# PWM.net
KiCad netlist of a schematic drawn in EAGLE
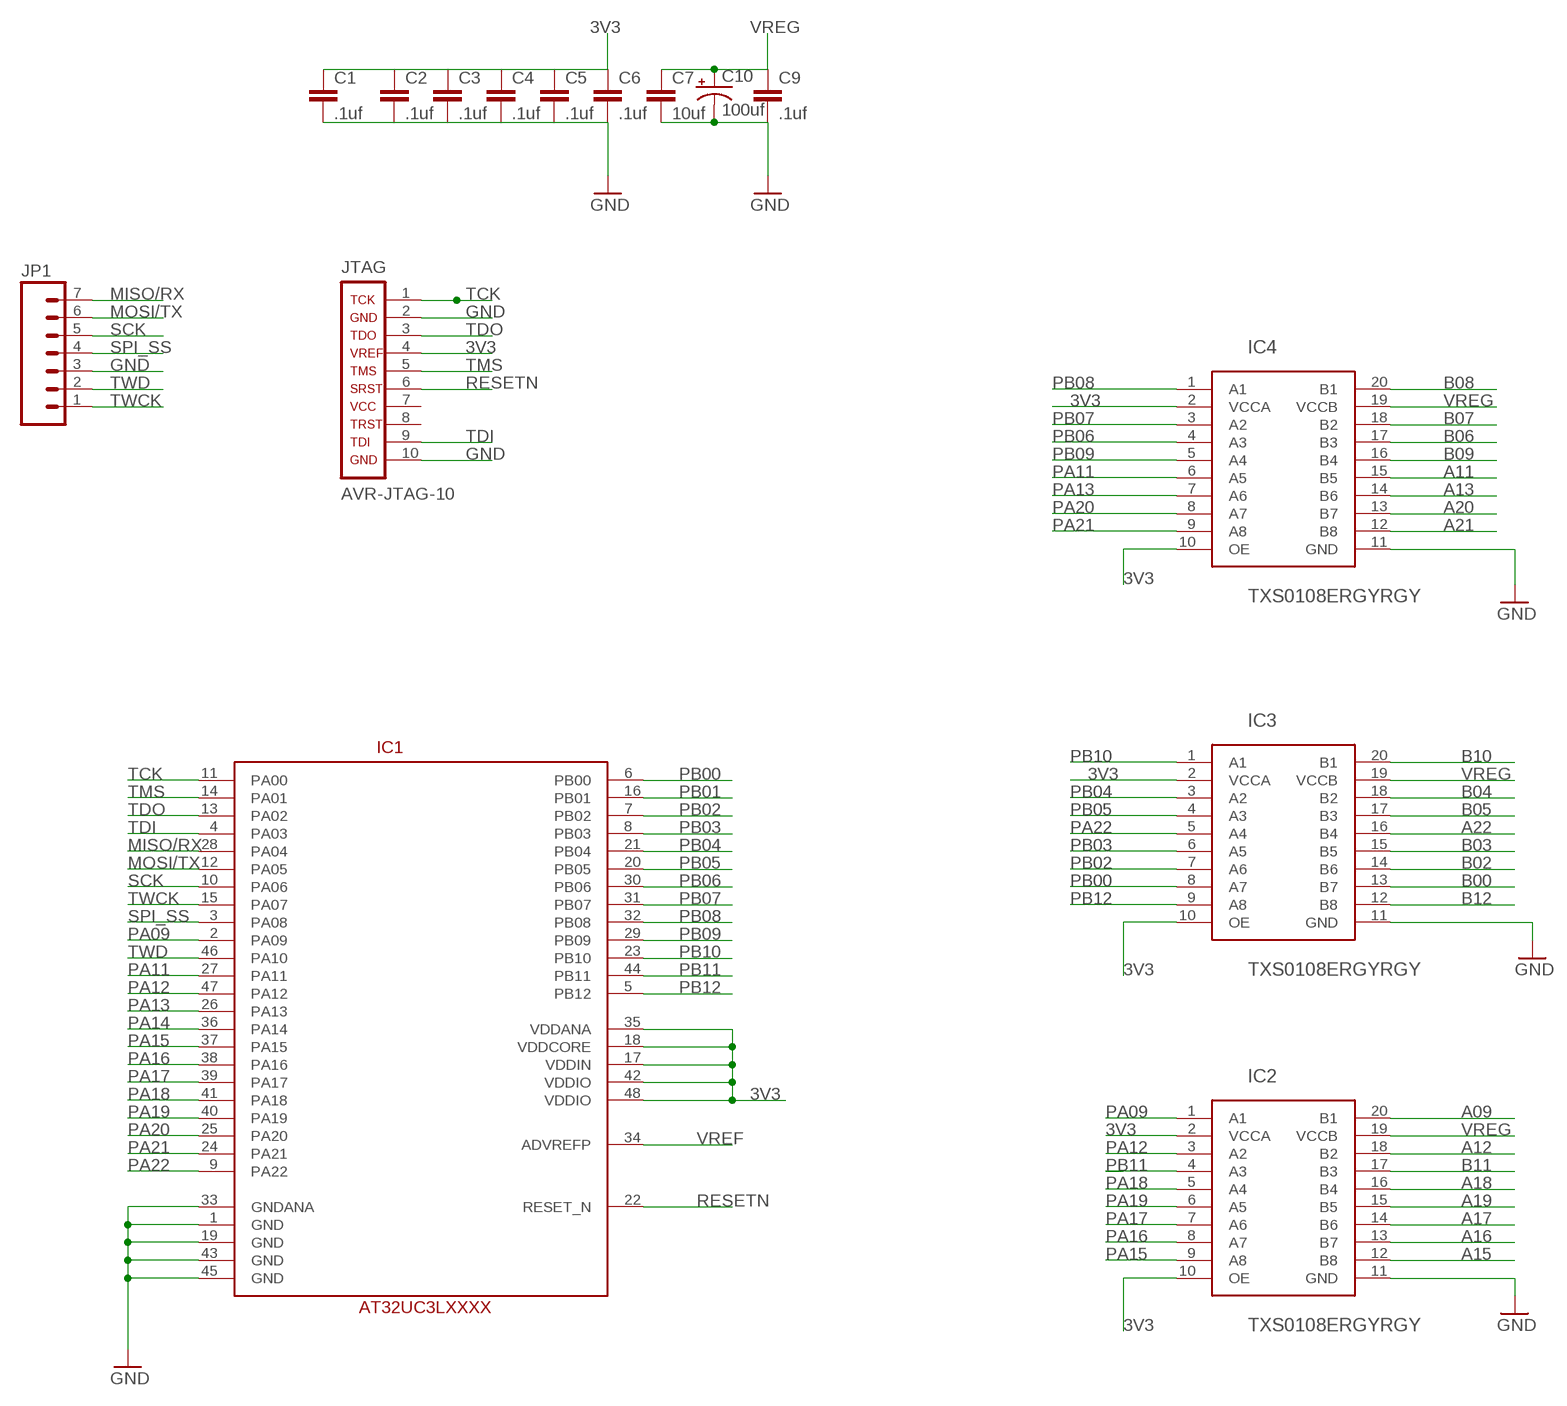
[diagram p0: schematic, sheet 1]
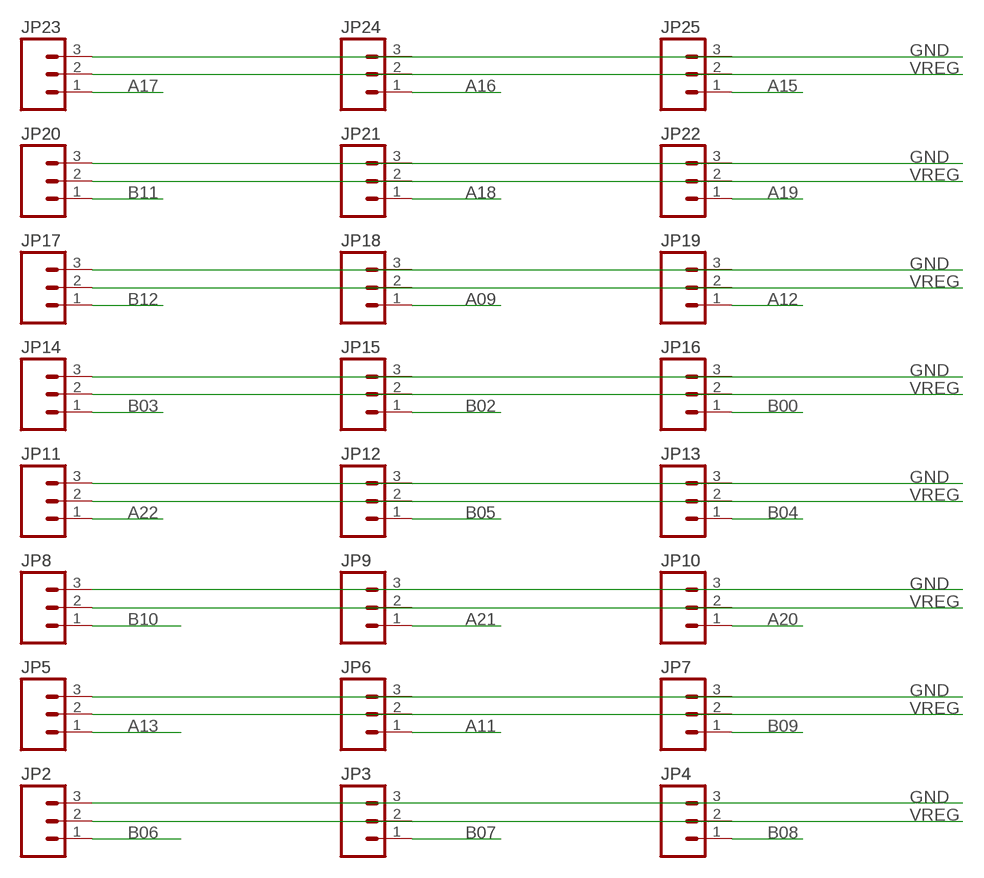
[diagram p1: schematic, sheet 2]
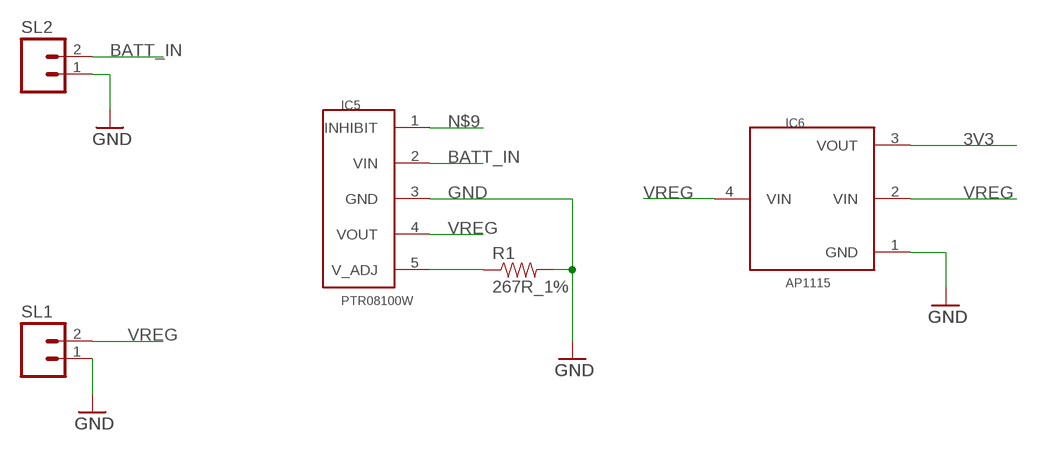
[diagram p2: schematic, sheet 3]

(export (version "E")
  (design (tool "Eeschema 10.0.6"))
  (components
    (comp (ref "IC5")
      (value "PTR08100W")
      (footprint "eagle-import:SLTS284E")
      (libsource (lib "eagle-import") (part "SLTS284ETI"))
    )
    (comp (ref "IC6")
      (value "AP1115")
      (footprint "eagle-import:SOT89-3L")
      (libsource (lib "eagle-import") (part "AP1115"))
    )
    (comp (ref "R1")
      (value "267R_1%")
      (footprint "eagle-import:0805")
      (libsource (lib "eagle-import") (part "RESISTOR0805-RES"))
    )
    (comp (ref "SL1")
      (value "M02")
      (footprint "eagle-import:02P")
      (libsource (lib "eagle-import") (part "M02"))
    )
    (comp (ref "SL2")
      (value "M02")
      (footprint "eagle-import:02P")
      (libsource (lib "eagle-import") (part "M02"))
    )
    (comp (ref "C1")
      (value ".1uf")
      (footprint "eagle-import:0805")
      (libsource (lib "eagle-import") (part "CAP0805"))
    )
    (comp (ref "C2")
      (value ".1uf")
      (footprint "eagle-import:0805")
      (libsource (lib "eagle-import") (part "CAP0805"))
    )
    (comp (ref "C3")
      (value ".1uf")
      (footprint "eagle-import:0805")
      (libsource (lib "eagle-import") (part "CAP0805"))
    )
    (comp (ref "C4")
      (value ".1uf")
      (footprint "eagle-import:0805")
      (libsource (lib "eagle-import") (part "CAP0805"))
    )
    (comp (ref "C5")
      (value ".1uf")
      (footprint "eagle-import:0805")
      (libsource (lib "eagle-import") (part "CAP0805"))
    )
    (comp (ref "C6")
      (value ".1uf")
      (footprint "eagle-import:0805")
      (libsource (lib "eagle-import") (part "CAP0805"))
    )
    (comp (ref "C7")
      (value "10uf")
      (footprint "eagle-import:0805")
      (libsource (lib "eagle-import") (part "CAP0805"))
    )
    (comp (ref "C9")
      (value ".1uf")
      (footprint "eagle-import:0805")
      (libsource (lib "eagle-import") (part "CAP0805"))
    )
    (comp (ref "C10")
      (value "100uf")
      (footprint "eagle-import:EIA7343")
      (libsource (lib "eagle-import") (part "CAP_POL7343"))
    )
    (comp (ref "IC1")
      (value "AT32UC3L016/32/64")
      (footprint "eagle-import:TQFP48")
      (libsource (lib "eagle-import") (part "AT32UC3L016/32/64"))
    )
    (comp (ref "IC2")
      (value "TXS0108ERGYRGY")
      (footprint "eagle-import:RGY")
      (libsource (lib "eagle-import") (part "TXS0108ERGYRGY"))
    )
    (comp (ref "IC3")
      (value "TXS0108ERGYRGY")
      (footprint "eagle-import:RGY")
      (libsource (lib "eagle-import") (part "TXS0108ERGYRGY"))
    )
    (comp (ref "IC4")
      (value "TXS0108ERGYRGY")
      (footprint "eagle-import:RGY")
      (libsource (lib "eagle-import") (part "TXS0108ERGYRGY"))
    )
    (comp (ref "JP1")
      (value "M07")
      (footprint "eagle-import:1X07")
      (libsource (lib "eagle-import") (part "M07"))
    )
    (comp (ref "JTAG")
      (value "AVR-JTAG-10")
      (footprint "eagle-import:AVR-JTAG-10")
      (libsource (lib "eagle-import") (part "AVR-JTAG-10"))
    )
    (comp (ref "JP2")
      (value "M03PTH")
      (footprint "eagle-import:1X03")
      (libsource (lib "eagle-import") (part "M03PTH"))
    )
    (comp (ref "JP3")
      (value "M03PTH")
      (footprint "eagle-import:1X03")
      (libsource (lib "eagle-import") (part "M03PTH"))
    )
    (comp (ref "JP4")
      (value "M03PTH")
      (footprint "eagle-import:1X03")
      (libsource (lib "eagle-import") (part "M03PTH"))
    )
    (comp (ref "JP5")
      (value "M03PTH")
      (footprint "eagle-import:1X03")
      (libsource (lib "eagle-import") (part "M03PTH"))
    )
    (comp (ref "JP6")
      (value "M03PTH")
      (footprint "eagle-import:1X03")
      (libsource (lib "eagle-import") (part "M03PTH"))
    )
    (comp (ref "JP7")
      (value "M03PTH")
      (footprint "eagle-import:1X03")
      (libsource (lib "eagle-import") (part "M03PTH"))
    )
    (comp (ref "JP8")
      (value "M03PTH")
      (footprint "eagle-import:1X03")
      (libsource (lib "eagle-import") (part "M03PTH"))
    )
    (comp (ref "JP9")
      (value "M03PTH")
      (footprint "eagle-import:1X03")
      (libsource (lib "eagle-import") (part "M03PTH"))
    )
    (comp (ref "JP10")
      (value "M03PTH")
      (footprint "eagle-import:1X03")
      (libsource (lib "eagle-import") (part "M03PTH"))
    )
    (comp (ref "JP11")
      (value "M03PTH")
      (footprint "eagle-import:1X03")
      (libsource (lib "eagle-import") (part "M03PTH"))
    )
    (comp (ref "JP12")
      (value "M03PTH")
      (footprint "eagle-import:1X03")
      (libsource (lib "eagle-import") (part "M03PTH"))
    )
    (comp (ref "JP13")
      (value "M03PTH")
      (footprint "eagle-import:1X03")
      (libsource (lib "eagle-import") (part "M03PTH"))
    )
    (comp (ref "JP14")
      (value "M03PTH")
      (footprint "eagle-import:1X03")
      (libsource (lib "eagle-import") (part "M03PTH"))
    )
    (comp (ref "JP15")
      (value "M03PTH")
      (footprint "eagle-import:1X03")
      (libsource (lib "eagle-import") (part "M03PTH"))
    )
    (comp (ref "JP16")
      (value "M03PTH")
      (footprint "eagle-import:1X03")
      (libsource (lib "eagle-import") (part "M03PTH"))
    )
    (comp (ref "JP17")
      (value "M03PTH")
      (footprint "eagle-import:1X03")
      (libsource (lib "eagle-import") (part "M03PTH"))
    )
    (comp (ref "JP18")
      (value "M03PTH")
      (footprint "eagle-import:1X03")
      (libsource (lib "eagle-import") (part "M03PTH"))
    )
    (comp (ref "JP19")
      (value "M03PTH")
      (footprint "eagle-import:1X03")
      (libsource (lib "eagle-import") (part "M03PTH"))
    )
    (comp (ref "JP20")
      (value "M03PTH")
      (footprint "eagle-import:1X03")
      (libsource (lib "eagle-import") (part "M03PTH"))
    )
    (comp (ref "JP21")
      (value "M03PTH")
      (footprint "eagle-import:1X03")
      (libsource (lib "eagle-import") (part "M03PTH"))
    )
    (comp (ref "JP22")
      (value "M03PTH")
      (footprint "eagle-import:1X03")
      (libsource (lib "eagle-import") (part "M03PTH"))
    )
    (comp (ref "JP23")
      (value "M03PTH")
      (footprint "eagle-import:1X03")
      (libsource (lib "eagle-import") (part "M03PTH"))
    )
    (comp (ref "JP24")
      (value "M03PTH")
      (footprint "eagle-import:1X03")
      (libsource (lib "eagle-import") (part "M03PTH"))
    )
    (comp (ref "JP25")
      (value "M03PTH")
      (footprint "eagle-import:1X03")
      (libsource (lib "eagle-import") (part "M03PTH"))
    )
  )
  (nets
    (net (code "1") (name "3V3") (class "Default")
      (node (ref "C1") (pin "1") (pinfunction "1_1") (pintype "passive"))
      (node (ref "C2") (pin "1") (pinfunction "1_1") (pintype "passive"))
      (node (ref "C3") (pin "1") (pinfunction "1_1") (pintype "passive"))
      (node (ref "C4") (pin "1") (pinfunction "1_1") (pintype "passive"))
      (node (ref "C5") (pin "1") (pinfunction "1_1") (pintype "passive"))
      (node (ref "C6") (pin "1") (pinfunction "1_1") (pintype "passive"))
      (node (ref "IC1") (pin "17") (pinfunction "VDDIN_17") (pintype "bidirectional"))
      (node (ref "IC1") (pin "18") (pinfunction "VDDCORE_18") (pintype "bidirectional"))
      (node (ref "IC1") (pin "35") (pinfunction "VDDANA_35") (pintype "bidirectional"))
      (node (ref "IC1") (pin "42") (pinfunction "VDDIO_42") (pintype "bidirectional"))
      (node (ref "IC1") (pin "48") (pinfunction "VDDIO_48") (pintype "bidirectional"))
      (node (ref "IC2") (pin "10") (pinfunction "OE_10") (pintype "bidirectional"))
      (node (ref "IC2") (pin "2") (pinfunction "VCCA_2") (pintype "bidirectional"))
      (node (ref "IC3") (pin "10") (pinfunction "OE_10") (pintype "bidirectional"))
      (node (ref "IC3") (pin "2") (pinfunction "VCCA_2") (pintype "bidirectional"))
      (node (ref "IC4") (pin "10") (pinfunction "OE_10") (pintype "bidirectional"))
      (node (ref "IC4") (pin "2") (pinfunction "VCCA_2") (pintype "bidirectional"))
      (node (ref "IC6") (pin "3") (pinfunction "VOUT_3") (pintype "bidirectional"))
      (node (ref "JTAG") (pin "4") (pinfunction "4_4") (pintype "passive"))
    )
    (net (code "2") (name "A09") (class "Default")
      (node (ref "IC2") (pin "20") (pinfunction "B1_20") (pintype "bidirectional"))
      (node (ref "JP18") (pin "1") (pinfunction "1_1") (pintype "passive"))
    )
    (net (code "3") (name "A11") (class "Default")
      (node (ref "IC4") (pin "15") (pinfunction "B5_15") (pintype "bidirectional"))
      (node (ref "JP6") (pin "1") (pinfunction "1_1") (pintype "passive"))
    )
    (net (code "4") (name "A12") (class "Default")
      (node (ref "IC2") (pin "18") (pinfunction "B2_18") (pintype "bidirectional"))
      (node (ref "JP19") (pin "1") (pinfunction "1_1") (pintype "passive"))
    )
    (net (code "5") (name "A13") (class "Default")
      (node (ref "IC4") (pin "14") (pinfunction "B6_14") (pintype "bidirectional"))
      (node (ref "JP5") (pin "1") (pinfunction "1_1") (pintype "passive"))
    )
    (net (code "6") (name "A15") (class "Default")
      (node (ref "IC2") (pin "12") (pinfunction "B8_12") (pintype "bidirectional"))
      (node (ref "JP25") (pin "1") (pinfunction "1_1") (pintype "passive"))
    )
    (net (code "7") (name "A16") (class "Default")
      (node (ref "IC2") (pin "13") (pinfunction "B7_13") (pintype "bidirectional"))
      (node (ref "JP24") (pin "1") (pinfunction "1_1") (pintype "passive"))
    )
    (net (code "8") (name "A17") (class "Default")
      (node (ref "IC2") (pin "14") (pinfunction "B6_14") (pintype "bidirectional"))
      (node (ref "JP23") (pin "1") (pinfunction "1_1") (pintype "passive"))
    )
    (net (code "9") (name "A18") (class "Default")
      (node (ref "IC2") (pin "16") (pinfunction "B4_16") (pintype "bidirectional"))
      (node (ref "JP21") (pin "1") (pinfunction "1_1") (pintype "passive"))
    )
    (net (code "10") (name "A19") (class "Default")
      (node (ref "IC2") (pin "15") (pinfunction "B5_15") (pintype "bidirectional"))
      (node (ref "JP22") (pin "1") (pinfunction "1_1") (pintype "passive"))
    )
    (net (code "11") (name "A20") (class "Default")
      (node (ref "IC4") (pin "13") (pinfunction "B7_13") (pintype "bidirectional"))
      (node (ref "JP10") (pin "1") (pinfunction "1_1") (pintype "passive"))
    )
    (net (code "12") (name "A21") (class "Default")
      (node (ref "IC4") (pin "12") (pinfunction "B8_12") (pintype "bidirectional"))
      (node (ref "JP9") (pin "1") (pinfunction "1_1") (pintype "passive"))
    )
    (net (code "13") (name "A22") (class "Default")
      (node (ref "IC3") (pin "16") (pinfunction "B4_16") (pintype "bidirectional"))
      (node (ref "JP11") (pin "1") (pinfunction "1_1") (pintype "passive"))
    )
    (net (code "14") (name "B00") (class "Default")
      (node (ref "IC3") (pin "13") (pinfunction "B7_13") (pintype "bidirectional"))
      (node (ref "JP16") (pin "1") (pinfunction "1_1") (pintype "passive"))
    )
    (net (code "15") (name "B02") (class "Default")
      (node (ref "IC3") (pin "14") (pinfunction "B6_14") (pintype "bidirectional"))
      (node (ref "JP15") (pin "1") (pinfunction "1_1") (pintype "passive"))
    )
    (net (code "16") (name "B03") (class "Default")
      (node (ref "IC3") (pin "15") (pinfunction "B5_15") (pintype "bidirectional"))
      (node (ref "JP14") (pin "1") (pinfunction "1_1") (pintype "passive"))
    )
    (net (code "17") (name "B04") (class "Default")
      (node (ref "IC3") (pin "18") (pinfunction "B2_18") (pintype "bidirectional"))
      (node (ref "JP13") (pin "1") (pinfunction "1_1") (pintype "passive"))
    )
    (net (code "18") (name "B05") (class "Default")
      (node (ref "IC3") (pin "17") (pinfunction "B3_17") (pintype "bidirectional"))
      (node (ref "JP12") (pin "1") (pinfunction "1_1") (pintype "passive"))
    )
    (net (code "19") (name "B06") (class "Default")
      (node (ref "IC4") (pin "17") (pinfunction "B3_17") (pintype "bidirectional"))
      (node (ref "JP2") (pin "1") (pinfunction "1_1") (pintype "passive"))
    )
    (net (code "20") (name "B07") (class "Default")
      (node (ref "IC4") (pin "18") (pinfunction "B2_18") (pintype "bidirectional"))
      (node (ref "JP3") (pin "1") (pinfunction "1_1") (pintype "passive"))
    )
    (net (code "21") (name "B08") (class "Default")
      (node (ref "IC4") (pin "20") (pinfunction "B1_20") (pintype "bidirectional"))
      (node (ref "JP4") (pin "1") (pinfunction "1_1") (pintype "passive"))
    )
    (net (code "22") (name "B09") (class "Default")
      (node (ref "IC4") (pin "16") (pinfunction "B4_16") (pintype "bidirectional"))
      (node (ref "JP7") (pin "1") (pinfunction "1_1") (pintype "passive"))
    )
    (net (code "23") (name "B10") (class "Default")
      (node (ref "IC3") (pin "20") (pinfunction "B1_20") (pintype "bidirectional"))
      (node (ref "JP8") (pin "1") (pinfunction "1_1") (pintype "passive"))
    )
    (net (code "24") (name "B11") (class "Default")
      (node (ref "IC2") (pin "17") (pinfunction "B3_17") (pintype "bidirectional"))
      (node (ref "JP20") (pin "1") (pinfunction "1_1") (pintype "passive"))
    )
    (net (code "25") (name "B12") (class "Default")
      (node (ref "IC3") (pin "12") (pinfunction "B8_12") (pintype "bidirectional"))
      (node (ref "JP17") (pin "1") (pinfunction "1_1") (pintype "passive"))
    )
    (net (code "26") (name "BATT_IN") (class "Default")
      (node (ref "IC5") (pin "2") (pinfunction "VIN_2") (pintype "bidirectional"))
      (node (ref "SL2") (pin "2") (pinfunction "2_2") (pintype "passive"))
    )
    (net (code "27") (name "GND") (class "Default")
      (node (ref "C1") (pin "2") (pinfunction "2_2") (pintype "passive"))
      (node (ref "C10") (pin "C") (pinfunction "-_C") (pintype "passive"))
      (node (ref "C2") (pin "2") (pinfunction "2_2") (pintype "passive"))
      (node (ref "C3") (pin "2") (pinfunction "2_2") (pintype "passive"))
      (node (ref "C4") (pin "2") (pinfunction "2_2") (pintype "passive"))
      (node (ref "C5") (pin "2") (pinfunction "2_2") (pintype "passive"))
      (node (ref "C6") (pin "2") (pinfunction "2_2") (pintype "passive"))
      (node (ref "C7") (pin "2") (pinfunction "2_2") (pintype "passive"))
      (node (ref "C9") (pin "2") (pinfunction "2_2") (pintype "passive"))
      (node (ref "IC1") (pin "1") (pinfunction "GND_1") (pintype "bidirectional"))
      (node (ref "IC1") (pin "19") (pinfunction "GND_19") (pintype "bidirectional"))
      (node (ref "IC1") (pin "33") (pinfunction "GNDANA_33") (pintype "bidirectional"))
      (node (ref "IC1") (pin "43") (pinfunction "GND_43") (pintype "bidirectional"))
      (node (ref "IC1") (pin "45") (pinfunction "GND_45") (pintype "bidirectional"))
      (node (ref "IC2") (pin "11") (pinfunction "GND_11") (pintype "bidirectional"))
      (node (ref "IC3") (pin "11") (pinfunction "GND_11") (pintype "bidirectional"))
      (node (ref "IC4") (pin "11") (pinfunction "GND_11") (pintype "bidirectional"))
      (node (ref "IC5") (pin "3") (pinfunction "GND_3") (pintype "bidirectional"))
      (node (ref "IC6") (pin "1") (pinfunction "GND_1") (pintype "bidirectional"))
      (node (ref "JP1") (pin "3") (pinfunction "3_3") (pintype "passive"))
      (node (ref "JP10") (pin "3") (pinfunction "3_3") (pintype "passive"))
      (node (ref "JP11") (pin "3") (pinfunction "3_3") (pintype "passive"))
      (node (ref "JP12") (pin "3") (pinfunction "3_3") (pintype "passive"))
      (node (ref "JP13") (pin "3") (pinfunction "3_3") (pintype "passive"))
      (node (ref "JP14") (pin "3") (pinfunction "3_3") (pintype "passive"))
      (node (ref "JP15") (pin "3") (pinfunction "3_3") (pintype "passive"))
      (node (ref "JP16") (pin "3") (pinfunction "3_3") (pintype "passive"))
      (node (ref "JP17") (pin "3") (pinfunction "3_3") (pintype "passive"))
      (node (ref "JP18") (pin "3") (pinfunction "3_3") (pintype "passive"))
      (node (ref "JP19") (pin "3") (pinfunction "3_3") (pintype "passive"))
      (node (ref "JP2") (pin "3") (pinfunction "3_3") (pintype "passive"))
      (node (ref "JP20") (pin "3") (pinfunction "3_3") (pintype "passive"))
      (node (ref "JP21") (pin "3") (pinfunction "3_3") (pintype "passive"))
      (node (ref "JP22") (pin "3") (pinfunction "3_3") (pintype "passive"))
      (node (ref "JP23") (pin "3") (pinfunction "3_3") (pintype "passive"))
      (node (ref "JP24") (pin "3") (pinfunction "3_3") (pintype "passive"))
      (node (ref "JP25") (pin "3") (pinfunction "3_3") (pintype "passive"))
      (node (ref "JP3") (pin "3") (pinfunction "3_3") (pintype "passive"))
      (node (ref "JP4") (pin "3") (pinfunction "3_3") (pintype "passive"))
      (node (ref "JP5") (pin "3") (pinfunction "3_3") (pintype "passive"))
      (node (ref "JP6") (pin "3") (pinfunction "3_3") (pintype "passive"))
      (node (ref "JP7") (pin "3") (pinfunction "3_3") (pintype "passive"))
      (node (ref "JP8") (pin "3") (pinfunction "3_3") (pintype "passive"))
      (node (ref "JP9") (pin "3") (pinfunction "3_3") (pintype "passive"))
      (node (ref "JTAG") (pin "10") (pinfunction "10_10") (pintype "passive"))
      (node (ref "JTAG") (pin "2") (pinfunction "2_2") (pintype "passive"))
      (node (ref "R1") (pin "2") (pinfunction "2_2") (pintype "passive"))
      (node (ref "SL1") (pin "1") (pinfunction "1_1") (pintype "passive"))
      (node (ref "SL2") (pin "1") (pinfunction "1_1") (pintype "passive"))
    )
    (net (code "28") (name "MISO{slash}RX") (class "Default")
      (node (ref "IC1") (pin "28") (pinfunction "PA04_28") (pintype "bidirectional"))
      (node (ref "JP1") (pin "7") (pinfunction "7_7") (pintype "passive"))
    )
    (net (code "29") (name "MOSI{slash}TX") (class "Default")
      (node (ref "IC1") (pin "12") (pinfunction "PA05_12") (pintype "bidirectional"))
      (node (ref "JP1") (pin "6") (pinfunction "6_6") (pintype "passive"))
    )
    (net (code "30") (name "N$9") (class "Default")
      (node (ref "IC5") (pin "1") (pinfunction "INHIBIT_1") (pintype "bidirectional"))
    )
    (net (code "31") (name "Net-(IC5-V_ADJ)") (class "Default")
      (node (ref "IC5") (pin "5") (pinfunction "V_ADJ_5") (pintype "bidirectional"))
      (node (ref "R1") (pin "1") (pinfunction "1_1") (pintype "passive"))
    )
    (net (code "32") (name "PA09") (class "Default")
      (node (ref "IC1") (pin "2") (pinfunction "PA09_2") (pintype "bidirectional"))
      (node (ref "IC2") (pin "1") (pinfunction "A1_1") (pintype "bidirectional"))
    )
    (net (code "33") (name "PA11") (class "Default")
      (node (ref "IC1") (pin "27") (pinfunction "PA11_27") (pintype "bidirectional"))
      (node (ref "IC4") (pin "6") (pinfunction "A5_6") (pintype "bidirectional"))
    )
    (net (code "34") (name "PA12") (class "Default")
      (node (ref "IC1") (pin "47") (pinfunction "PA12_47") (pintype "bidirectional"))
      (node (ref "IC2") (pin "3") (pinfunction "A2_3") (pintype "bidirectional"))
    )
    (net (code "35") (name "PA13") (class "Default")
      (node (ref "IC1") (pin "26") (pinfunction "PA13_26") (pintype "bidirectional"))
      (node (ref "IC4") (pin "7") (pinfunction "A6_7") (pintype "bidirectional"))
    )
    (net (code "36") (name "PA14") (class "Default")
      (node (ref "IC1") (pin "36") (pinfunction "PA14_36") (pintype "bidirectional"))
    )
    (net (code "37") (name "PA15") (class "Default")
      (node (ref "IC1") (pin "37") (pinfunction "PA15_37") (pintype "bidirectional"))
      (node (ref "IC2") (pin "9") (pinfunction "A8_9") (pintype "bidirectional"))
    )
    (net (code "38") (name "PA16") (class "Default")
      (node (ref "IC1") (pin "38") (pinfunction "PA16_38") (pintype "bidirectional"))
      (node (ref "IC2") (pin "8") (pinfunction "A7_8") (pintype "bidirectional"))
    )
    (net (code "39") (name "PA17") (class "Default")
      (node (ref "IC1") (pin "39") (pinfunction "PA17_39") (pintype "bidirectional"))
      (node (ref "IC2") (pin "7") (pinfunction "A6_7") (pintype "bidirectional"))
    )
    (net (code "40") (name "PA18") (class "Default")
      (node (ref "IC1") (pin "41") (pinfunction "PA18_41") (pintype "bidirectional"))
      (node (ref "IC2") (pin "5") (pinfunction "A4_5") (pintype "bidirectional"))
    )
    (net (code "41") (name "PA19") (class "Default")
      (node (ref "IC1") (pin "40") (pinfunction "PA19_40") (pintype "bidirectional"))
      (node (ref "IC2") (pin "6") (pinfunction "A5_6") (pintype "bidirectional"))
    )
    (net (code "42") (name "PA20") (class "Default")
      (node (ref "IC1") (pin "25") (pinfunction "PA20_25") (pintype "bidirectional"))
      (node (ref "IC4") (pin "8") (pinfunction "A7_8") (pintype "bidirectional"))
    )
    (net (code "43") (name "PA21") (class "Default")
      (node (ref "IC1") (pin "24") (pinfunction "PA21_24") (pintype "bidirectional"))
      (node (ref "IC4") (pin "9") (pinfunction "A8_9") (pintype "bidirectional"))
    )
    (net (code "44") (name "PA22") (class "Default")
      (node (ref "IC1") (pin "9") (pinfunction "PA22_9") (pintype "bidirectional"))
      (node (ref "IC3") (pin "5") (pinfunction "A4_5") (pintype "bidirectional"))
    )
    (net (code "45") (name "PB00") (class "Default")
      (node (ref "IC1") (pin "6") (pinfunction "PB00_6") (pintype "bidirectional"))
      (node (ref "IC3") (pin "8") (pinfunction "A7_8") (pintype "bidirectional"))
    )
    (net (code "46") (name "PB01") (class "Default")
      (node (ref "IC1") (pin "16") (pinfunction "PB01_16") (pintype "bidirectional"))
    )
    (net (code "47") (name "PB02") (class "Default")
      (node (ref "IC1") (pin "7") (pinfunction "PB02_7") (pintype "bidirectional"))
      (node (ref "IC3") (pin "7") (pinfunction "A6_7") (pintype "bidirectional"))
    )
    (net (code "48") (name "PB03") (class "Default")
      (node (ref "IC1") (pin "8") (pinfunction "PB03_8") (pintype "bidirectional"))
      (node (ref "IC3") (pin "6") (pinfunction "A5_6") (pintype "bidirectional"))
    )
    (net (code "49") (name "PB04") (class "Default")
      (node (ref "IC1") (pin "21") (pinfunction "PB04_21") (pintype "bidirectional"))
      (node (ref "IC3") (pin "3") (pinfunction "A2_3") (pintype "bidirectional"))
    )
    (net (code "50") (name "PB05") (class "Default")
      (node (ref "IC1") (pin "20") (pinfunction "PB05_20") (pintype "bidirectional"))
      (node (ref "IC3") (pin "4") (pinfunction "A3_4") (pintype "bidirectional"))
    )
    (net (code "51") (name "PB06") (class "Default")
      (node (ref "IC1") (pin "30") (pinfunction "PB06_30") (pintype "bidirectional"))
      (node (ref "IC4") (pin "4") (pinfunction "A3_4") (pintype "bidirectional"))
    )
    (net (code "52") (name "PB07") (class "Default")
      (node (ref "IC1") (pin "31") (pinfunction "PB07_31") (pintype "bidirectional"))
      (node (ref "IC4") (pin "3") (pinfunction "A2_3") (pintype "bidirectional"))
    )
    (net (code "53") (name "PB08") (class "Default")
      (node (ref "IC1") (pin "32") (pinfunction "PB08_32") (pintype "bidirectional"))
      (node (ref "IC4") (pin "1") (pinfunction "A1_1") (pintype "bidirectional"))
    )
    (net (code "54") (name "PB09") (class "Default")
      (node (ref "IC1") (pin "29") (pinfunction "PB09_29") (pintype "bidirectional"))
      (node (ref "IC4") (pin "5") (pinfunction "A4_5") (pintype "bidirectional"))
    )
    (net (code "55") (name "PB10") (class "Default")
      (node (ref "IC1") (pin "23") (pinfunction "PB10_23") (pintype "bidirectional"))
      (node (ref "IC3") (pin "1") (pinfunction "A1_1") (pintype "bidirectional"))
    )
    (net (code "56") (name "PB11") (class "Default")
      (node (ref "IC1") (pin "44") (pinfunction "PB11_44") (pintype "bidirectional"))
      (node (ref "IC2") (pin "4") (pinfunction "A3_4") (pintype "bidirectional"))
    )
    (net (code "57") (name "PB12") (class "Default")
      (node (ref "IC1") (pin "5") (pinfunction "PB12_5") (pintype "bidirectional"))
      (node (ref "IC3") (pin "9") (pinfunction "A8_9") (pintype "bidirectional"))
    )
    (net (code "58") (name "RESETN") (class "Default")
      (node (ref "IC1") (pin "22") (pinfunction "RESET_N_22") (pintype "bidirectional"))
      (node (ref "JTAG") (pin "6") (pinfunction "6_6") (pintype "passive"))
    )
    (net (code "59") (name "SCK") (class "Default")
      (node (ref "IC1") (pin "10") (pinfunction "PA06_10") (pintype "bidirectional"))
      (node (ref "JP1") (pin "5") (pinfunction "5_5") (pintype "passive"))
    )
    (net (code "60") (name "SPI_SS") (class "Default")
      (node (ref "IC1") (pin "3") (pinfunction "PA08_3") (pintype "bidirectional"))
      (node (ref "JP1") (pin "4") (pinfunction "4_4") (pintype "passive"))
    )
    (net (code "61") (name "TCK") (class "Default")
      (node (ref "IC1") (pin "11") (pinfunction "PA00_11") (pintype "bidirectional"))
      (node (ref "JTAG") (pin "1") (pinfunction "1_1") (pintype "passive"))
    )
    (net (code "62") (name "TDI") (class "Default")
      (node (ref "IC1") (pin "4") (pinfunction "PA03_4") (pintype "bidirectional"))
      (node (ref "JTAG") (pin "9") (pinfunction "9_9") (pintype "passive"))
    )
    (net (code "63") (name "TDO") (class "Default")
      (node (ref "IC1") (pin "13") (pinfunction "PA02_13") (pintype "bidirectional"))
      (node (ref "JTAG") (pin "3") (pinfunction "3_3") (pintype "passive"))
    )
    (net (code "64") (name "TMS") (class "Default")
      (node (ref "IC1") (pin "14") (pinfunction "PA01_14") (pintype "bidirectional"))
      (node (ref "JTAG") (pin "5") (pinfunction "5_5") (pintype "passive"))
    )
    (net (code "65") (name "TWCK") (class "Default")
      (node (ref "IC1") (pin "15") (pinfunction "PA07_15") (pintype "bidirectional"))
      (node (ref "JP1") (pin "1") (pinfunction "1_1") (pintype "passive"))
    )
    (net (code "66") (name "TWD") (class "Default")
      (node (ref "IC1") (pin "46") (pinfunction "PA10_46") (pintype "bidirectional"))
      (node (ref "JP1") (pin "2") (pinfunction "2_2") (pintype "passive"))
    )
    (net (code "67") (name "VREF") (class "Default")
      (node (ref "IC1") (pin "34") (pinfunction "ADVREFP_34") (pintype "bidirectional"))
    )
    (net (code "68") (name "VREG") (class "Default")
      (node (ref "C10") (pin "A") (pinfunction "+_A") (pintype "passive"))
      (node (ref "C7") (pin "1") (pinfunction "1_1") (pintype "passive"))
      (node (ref "C9") (pin "1") (pinfunction "1_1") (pintype "passive"))
      (node (ref "IC2") (pin "19") (pinfunction "VCCB_19") (pintype "bidirectional"))
      (node (ref "IC3") (pin "19") (pinfunction "VCCB_19") (pintype "bidirectional"))
      (node (ref "IC4") (pin "19") (pinfunction "VCCB_19") (pintype "bidirectional"))
      (node (ref "IC5") (pin "4") (pinfunction "VOUT_4") (pintype "bidirectional"))
      (node (ref "IC6") (pin "2") (pinfunction "VIN_2") (pintype "bidirectional"))
      (node (ref "IC6") (pin "4") (pinfunction "VIN_4") (pintype "bidirectional"))
      (node (ref "JP10") (pin "2") (pinfunction "2_2") (pintype "passive"))
      (node (ref "JP11") (pin "2") (pinfunction "2_2") (pintype "passive"))
      (node (ref "JP12") (pin "2") (pinfunction "2_2") (pintype "passive"))
      (node (ref "JP13") (pin "2") (pinfunction "2_2") (pintype "passive"))
      (node (ref "JP14") (pin "2") (pinfunction "2_2") (pintype "passive"))
      (node (ref "JP15") (pin "2") (pinfunction "2_2") (pintype "passive"))
      (node (ref "JP16") (pin "2") (pinfunction "2_2") (pintype "passive"))
      (node (ref "JP17") (pin "2") (pinfunction "2_2") (pintype "passive"))
      (node (ref "JP18") (pin "2") (pinfunction "2_2") (pintype "passive"))
      (node (ref "JP19") (pin "2") (pinfunction "2_2") (pintype "passive"))
      (node (ref "JP2") (pin "2") (pinfunction "2_2") (pintype "passive"))
      (node (ref "JP20") (pin "2") (pinfunction "2_2") (pintype "passive"))
      (node (ref "JP21") (pin "2") (pinfunction "2_2") (pintype "passive"))
      (node (ref "JP22") (pin "2") (pinfunction "2_2") (pintype "passive"))
      (node (ref "JP23") (pin "2") (pinfunction "2_2") (pintype "passive"))
      (node (ref "JP24") (pin "2") (pinfunction "2_2") (pintype "passive"))
      (node (ref "JP25") (pin "2") (pinfunction "2_2") (pintype "passive"))
      (node (ref "JP3") (pin "2") (pinfunction "2_2") (pintype "passive"))
      (node (ref "JP4") (pin "2") (pinfunction "2_2") (pintype "passive"))
      (node (ref "JP5") (pin "2") (pinfunction "2_2") (pintype "passive"))
      (node (ref "JP6") (pin "2") (pinfunction "2_2") (pintype "passive"))
      (node (ref "JP7") (pin "2") (pinfunction "2_2") (pintype "passive"))
      (node (ref "JP8") (pin "2") (pinfunction "2_2") (pintype "passive"))
      (node (ref "JP9") (pin "2") (pinfunction "2_2") (pintype "passive"))
      (node (ref "SL1") (pin "2") (pinfunction "2_2") (pintype "passive"))
    )
    (net (code "69") (name "unconnected-(JTAG-Pad7)") (class "Default")
      (node (ref "JTAG") (pin "7") (pinfunction "7_7") (pintype "passive"))
    )
    (net (code "70") (name "unconnected-(JTAG-Pad8)") (class "Default")
      (node (ref "JTAG") (pin "8") (pinfunction "8_8") (pintype "passive"))
    )
  )
)
